# sequence_panel.net
KiCad netlist of a schematic drawn in EAGLE
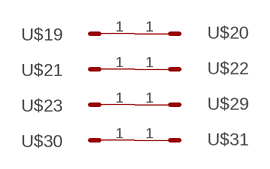
[diagram p0: schematic, sheet 1]

(export (version "E")
  (design (tool "Eeschema 10.0.6"))
  (components
    (comp (ref "U$19")
      (value "HEADER/MALE/01")
      (footprint "eagle-import:HEADER_MALE_01")
      (libsource (lib "eagle-import") (part "HEADER/MALE/01"))
    )
    (comp (ref "U$20")
      (value "HEADER/MALE/01")
      (footprint "eagle-import:HEADER_MALE_01")
      (libsource (lib "eagle-import") (part "HEADER/MALE/01"))
    )
    (comp (ref "U$21")
      (value "HEADER/MALE/01")
      (footprint "eagle-import:HEADER_MALE_01")
      (libsource (lib "eagle-import") (part "HEADER/MALE/01"))
    )
    (comp (ref "U$22")
      (value "HEADER/MALE/01")
      (footprint "eagle-import:HEADER_MALE_01")
      (libsource (lib "eagle-import") (part "HEADER/MALE/01"))
    )
    (comp (ref "U$23")
      (value "HEADER/MALE/01")
      (footprint "eagle-import:HEADER_MALE_01")
      (libsource (lib "eagle-import") (part "HEADER/MALE/01"))
    )
    (comp (ref "U$29")
      (value "HEADER/MALE/01")
      (footprint "eagle-import:HEADER_MALE_01")
      (libsource (lib "eagle-import") (part "HEADER/MALE/01"))
    )
    (comp (ref "U$30")
      (value "HEADER/MALE/01")
      (footprint "eagle-import:HEADER_MALE_01")
      (libsource (lib "eagle-import") (part "HEADER/MALE/01"))
    )
    (comp (ref "U$31")
      (value "HEADER/MALE/01")
      (footprint "eagle-import:HEADER_MALE_01")
      (libsource (lib "eagle-import") (part "HEADER/MALE/01"))
    )
  )
  (nets
    (net (code "1") (name "Net-(U$19-3)") (class "Default")
      (node (ref "U$19") (pin "1") (pinfunction "3_1") (pintype "passive"))
      (node (ref "U$20") (pin "1") (pinfunction "3_1") (pintype "passive"))
    )
    (net (code "2") (name "Net-(U$21-3)") (class "Default")
      (node (ref "U$21") (pin "1") (pinfunction "3_1") (pintype "passive"))
      (node (ref "U$22") (pin "1") (pinfunction "3_1") (pintype "passive"))
    )
    (net (code "3") (name "Net-(U$23-3)") (class "Default")
      (node (ref "U$23") (pin "1") (pinfunction "3_1") (pintype "passive"))
      (node (ref "U$29") (pin "1") (pinfunction "3_1") (pintype "passive"))
    )
    (net (code "4") (name "Net-(U$30-3)") (class "Default")
      (node (ref "U$30") (pin "1") (pinfunction "3_1") (pintype "passive"))
      (node (ref "U$31") (pin "1") (pinfunction "3_1") (pintype "passive"))
    )
  )
)
